# H01R0_Backend.net
KiCad netlist of a schematic drawn in Altium Designer
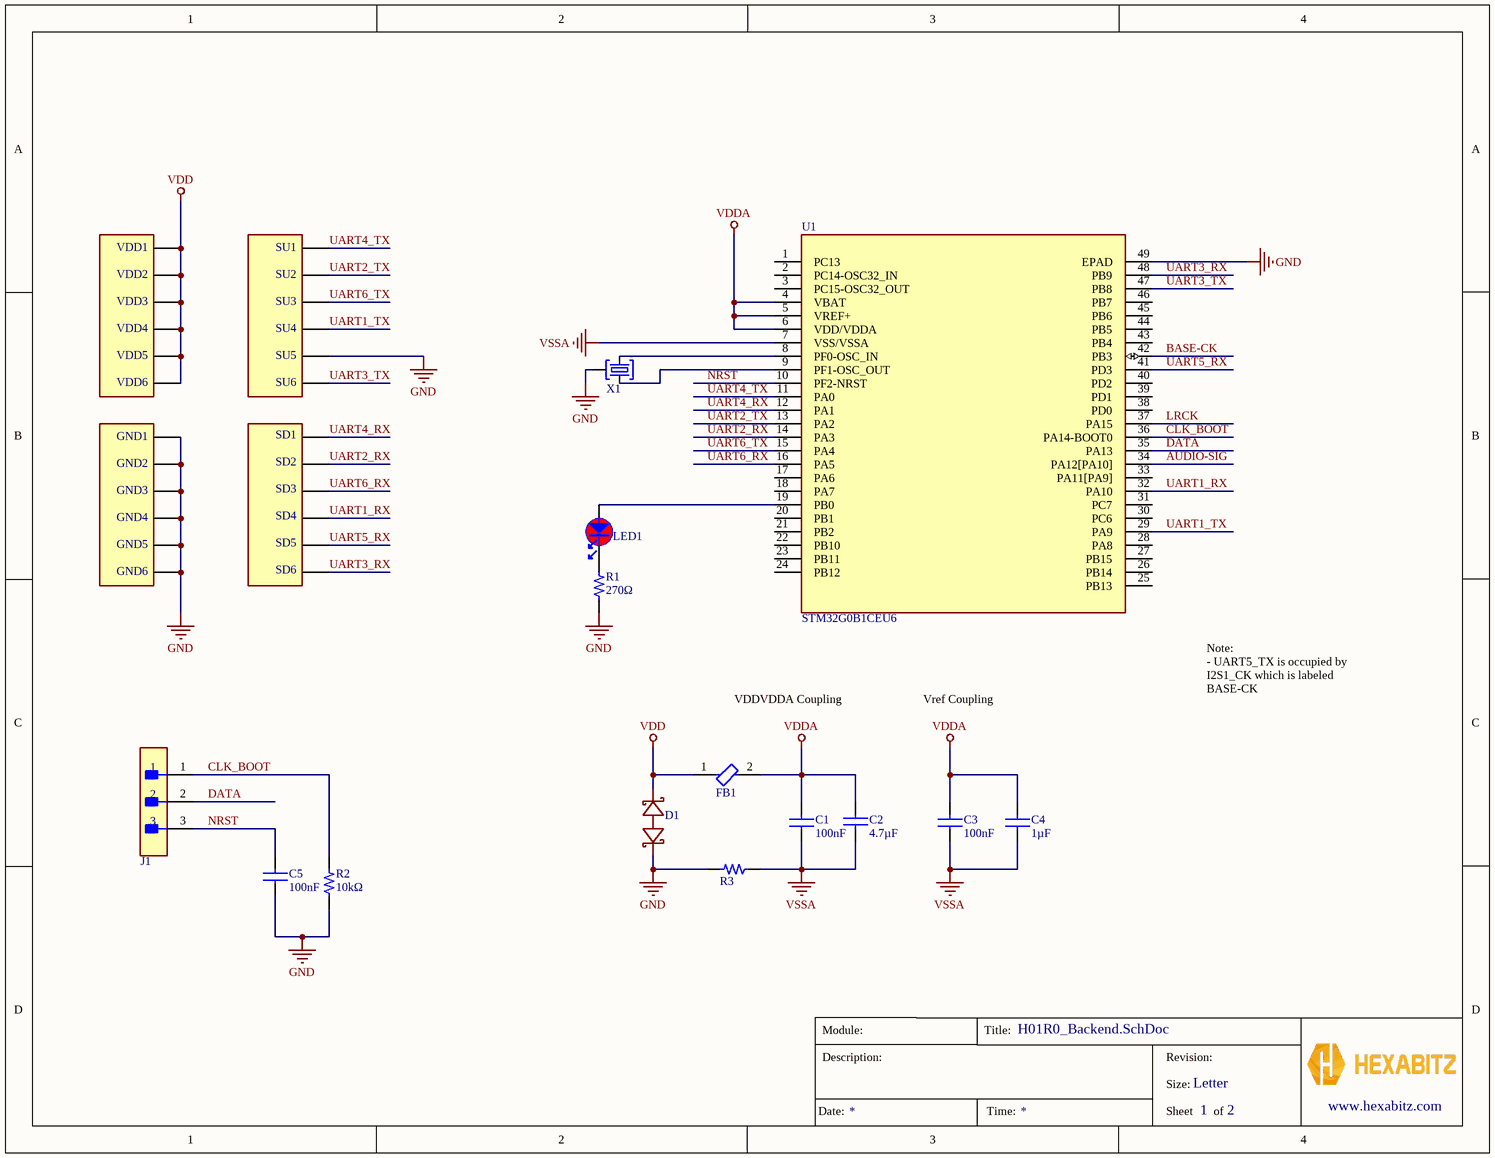
[diagram p0: H01R0_Backend.SchDoc]

(export (version "E")
  (design (tool "Eeschema 10.0.6"))
  (components
    (comp (ref "C1")
      (value "100nF")
      (footprint "C0603")
      (fields
        (field (name "MANUFACTURER") "Samsung Electro-Mechanics")
        (field (name "MANUFACTURER PART NUMBER") "CL10B104KA8NNNC")
        (field (name "TOLERANCE") "10%")
      )
      (libsource (lib "Hexabitz Altium Library") (part "generic Capacitor"))
    )
    (comp (ref "C2")
      (value "4.7µF")
      (footprint "C0805")
      (fields
        (field (name "MANUFACTURER") "Samsung Electro-Mechanics")
        (field (name "MANUFACTURER PART NUMBER") "CL21X475KAQNNNE")
        (field (name "TOLERANCE") "10%")
      )
      (libsource (lib "Hexabitz Altium Library") (part "generic Capacitor"))
    )
    (comp (ref "C3")
      (value "100nF")
      (footprint "C0603")
      (fields
        (field (name "MANUFACTURER") "Samsung Electro-Mechanics")
        (field (name "MANUFACTURER PART NUMBER") "CL10B104KA8NNNC")
        (field (name "TOLERANCE") "10%")
      )
      (libsource (lib "Hexabitz Altium Library") (part "generic Capacitor"))
    )
    (comp (ref "C4")
      (value "1µF")
      (footprint "C0805")
      (description "Ceramic Capacitor, Ceramic, 16V, 10% +Tol, 10% -Tol, X7R, 15% TC, 1uF, Surface Mount, 0805")
      (fields
        (field (name "MANUFACTURER") "Yageo Group")
        (field (name "MANUFACTURER PART NUMBER") "CC0805KKX7R7BB105")
      )
      (libsource (lib "Hexabitz Altium Library") (part "generic Capacitor"))
    )
    (comp (ref "C5")
      (value "100nF")
      (footprint "C0603")
      (fields
        (field (name "MANUFACTURER") "Samsung Electro-Mechanics")
        (field (name "MANUFACTURER PART NUMBER") "CL10B104KA8NNNC")
        (field (name "TOLERANCE") "10%")
      )
      (libsource (lib "Hexabitz Altium Library") (part "generic Capacitor"))
    )
    (comp (ref "D1")
      (value "CDSOD323-T03SC")
      (footprint "SOD2513X114N")
      (description "A 3V, 350W, bi-directional, standard capacitance, SOD323 pkg TVS Diode ¦ Bourns CDSOD323-T03SC")
      (fields (field (name "MANUFACTURER") "Bourns"))
      (libsource (lib "Hexabitz Altium Library") (part "CDSOD323-T03SC"))
    )
    (comp (ref "FB1")
      (value "MMZ1608Y300B")
      (footprint "FP-MMZ1608-0_8-MFG")
      (description "Ferrite Beads 0603 30ohms 1500mA Signal Line AEC-Q200")
      (fields
        (field (name "MANUFACTURER") "TDK")
        (field (name "MANUFACTURER PART NUMBER") "MMZ1608Y300BTD25")
      )
      (libsource (lib "Hexabitz Altium Library") (part "MMZ1608Y300B"))
    )
    (comp (ref "GND1")
      (value "HEXABIT_UART_PORT")
      (footprint "HEXABIT_POWER_PORT_D")
      (libsource (lib "hexabitz_connectors.Library") (part "HEXABIT_POWER_PORT_D"))
    )
    (comp (ref "GND2")
      (value "HEXABIT_UART_PORT")
      (footprint "HEXABIT_POWER_PORT_D")
      (libsource (lib "hexabitz_connectors.Library") (part "HEXABIT_POWER_PORT_D"))
    )
    (comp (ref "GND3")
      (value "HEXABIT_UART_PORT")
      (footprint "HEXABIT_POWER_PORT_D")
      (libsource (lib "hexabitz_connectors.Library") (part "HEXABIT_POWER_PORT_D"))
    )
    (comp (ref "GND4")
      (value "HEXABIT_UART_PORT")
      (footprint "HEXABIT_POWER_PORT_D")
      (libsource (lib "hexabitz_connectors.Library") (part "HEXABIT_POWER_PORT_D"))
    )
    (comp (ref "GND5")
      (value "HEXABIT_UART_PORT")
      (footprint "HEXABIT_POWER_PORT_D")
      (libsource (lib "hexabitz_connectors.Library") (part "HEXABIT_POWER_PORT_D"))
    )
    (comp (ref "GND6")
      (value "HEXABIT_UART_PORT")
      (footprint "HEXABIT_POWER_PORT_D")
      (libsource (lib "hexabitz_connectors.Library") (part "HEXABIT_POWER_PORT_D"))
    )
    (comp (ref "J1")
      (value "TSW-103-14-G-S")
      (footprint "FP-TSW-103-14-G-S-MFG")
      (description "CONN HEADER VERT 3POS 2.54MM")
      (libsource (lib "Altium Content Vault") (part "cd3439d6ef35ae5d9b27ec4fdd3e828"))
    )
    (comp (ref "LED1")
      (value "VLMS1300-GS08")
      (footprint "FP-6_541-5092_01-4-MFG")
      (description "LED Uni-Color Super Red 639nm 2-Pin Chip 0603(1608Metric) T/R")
      (fields (field (name "MANUFACTURER") "Vishay Semiconductors"))
      (libsource (lib "Hexabitz Altium Library") (part "VLMS1300-GS08"))
    )
    (comp (ref "R1")
      (value "270Ω")
      (footprint "R0603")
      (description "Res Thick Film 0603 270 Ohm 5% 0.1W(1/10W) ±200ppm/C Pad SMD Automotive T/R")
      (fields
        (field (name "MANUFACTURER") "Panasonic")
        (field (name "MANUFACTURER PART NUMBER") "ERJ-3GEYJ271V")
      )
      (libsource (lib "Hexabitz Altium Library") (part "generic Resistor"))
    )
    (comp (ref "R2")
      (value "10kΩ")
      (footprint "R0603")
      (description "100mW Thick Film Resistors ±100ppm/℃ ±1% 10kΩ 0603 Chip Resistor - Surface Mount ROHS")
      (fields
        (field (name "MANUFACTURER") "Yageo Group")
        (field (name "MANUFACTURER PART NUMBER") "RC0603FR-0710KL")
      )
      (libsource (lib "") (part "generic Resistor_2"))
    )
    (comp (ref "R3")
      (value "Manufacturer Part Number")
      (footprint "R0603")
      (libsource (lib "") (part "generic Resistor_1"))
    )
    (comp (ref "SD1")
      (value "HEXABIT_UART_PORT")
      (footprint "HEXABIT_UART_PORT_D")
      (libsource (lib "hexabitz_connectors.Library") (part "HEXABIT_UART_PORT_D"))
    )
    (comp (ref "SD2")
      (value "HEXABIT_UART_PORT")
      (footprint "HEXABIT_UART_PORT_D")
      (libsource (lib "hexabitz_connectors.Library") (part "HEXABIT_UART_PORT_D"))
    )
    (comp (ref "SD3")
      (value "HEXABIT_UART_PORT")
      (footprint "HEXABIT_UART_PORT_D")
      (libsource (lib "hexabitz_connectors.Library") (part "HEXABIT_UART_PORT_D"))
    )
    (comp (ref "SD4")
      (value "HEXABIT_UART_PORT")
      (footprint "HEXABIT_UART_PORT_D")
      (libsource (lib "hexabitz_connectors.Library") (part "HEXABIT_UART_PORT_D"))
    )
    (comp (ref "SD5")
      (value "HEXABIT_UART_PORT")
      (footprint "HEXABIT_UART_PORT_D")
      (libsource (lib "hexabitz_connectors.Library") (part "HEXABIT_UART_PORT_D"))
    )
    (comp (ref "SD6")
      (value "HEXABIT_UART_PORT")
      (footprint "HEXABIT_UART_PORT_D")
      (libsource (lib "hexabitz_connectors.Library") (part "HEXABIT_UART_PORT_D"))
    )
    (comp (ref "SU1")
      (value "HEXABIT_UART_PORT")
      (footprint "HEXABIT_UART_PORT_U")
      (libsource (lib "hexabitz_connectors.Library") (part "HEXABIT_UART_PORT_U"))
    )
    (comp (ref "SU2")
      (value "HEXABIT_UART_PORT")
      (footprint "HEXABIT_UART_PORT_U")
      (libsource (lib "hexabitz_connectors.Library") (part "HEXABIT_UART_PORT_U"))
    )
    (comp (ref "SU3")
      (value "HEXABIT_UART_PORT")
      (footprint "HEXABIT_UART_PORT_U")
      (libsource (lib "hexabitz_connectors.Library") (part "HEXABIT_UART_PORT_U"))
    )
    (comp (ref "SU4")
      (value "HEXABIT_UART_PORT")
      (footprint "HEXABIT_UART_PORT_U")
      (libsource (lib "hexabitz_connectors.Library") (part "HEXABIT_UART_PORT_U"))
    )
    (comp (ref "SU5")
      (value "HEXABIT_UART_PORT")
      (footprint "HEXABIT_UART_PORT_U")
      (libsource (lib "hexabitz_connectors.Library") (part "HEXABIT_UART_PORT_U"))
    )
    (comp (ref "SU6")
      (value "HEXABIT_UART_PORT")
      (footprint "HEXABIT_UART_PORT_U")
      (libsource (lib "hexabitz_connectors.Library") (part "HEXABIT_UART_PORT_U"))
    )
    (comp (ref "U1")
      (value "STM32G0B1CEU6")
      (footprint "QFN50P700X700X65-49N-D")
      (description "MCU 32-bit ARM Cortex M0+ RISC 512KB Flash 1.8V/2.5V/3.3V 48-Pin UFQFPN EP Tray")
      (fields
        (field (name "MANUFACTURER") "STMicroelectronics")
        (field (name "MANUFACTURER PART NUMBER") "STM32G0B1CEU6")
      )
      (libsource (lib "Hexabitz Altium Library") (part "STM32G0B1CEU6"))
    )
    (comp (ref "VDD1")
      (value "HEXABIT_UART_PORT")
      (footprint "HEXABIT_POWER_PORT_U")
      (libsource (lib "hexabitz_connectors.Library") (part "HEXABIT_POWER_PORT_U"))
    )
    (comp (ref "VDD2")
      (value "HEXABIT_UART_PORT")
      (footprint "HEXABIT_POWER_PORT_U")
      (libsource (lib "hexabitz_connectors.Library") (part "HEXABIT_POWER_PORT_U"))
    )
    (comp (ref "VDD3")
      (value "HEXABIT_UART_PORT")
      (footprint "HEXABIT_POWER_PORT_U")
      (libsource (lib "hexabitz_connectors.Library") (part "HEXABIT_POWER_PORT_U"))
    )
    (comp (ref "VDD4")
      (value "HEXABIT_UART_PORT")
      (footprint "HEXABIT_POWER_PORT_U")
      (libsource (lib "hexabitz_connectors.Library") (part "HEXABIT_POWER_PORT_U"))
    )
    (comp (ref "VDD5")
      (value "HEXABIT_UART_PORT")
      (footprint "HEXABIT_POWER_PORT_U")
      (libsource (lib "hexabitz_connectors.Library") (part "HEXABIT_POWER_PORT_U"))
    )
    (comp (ref "VDD6")
      (value "HEXABIT_UART_PORT")
      (footprint "HEXABIT_POWER_PORT_U")
      (libsource (lib "hexabitz_connectors.Library") (part "HEXABIT_POWER_PORT_U"))
    )
    (comp (ref "X1")
      (value "CSTCE8M00G52Z-R0")
      (footprint "XTALL_CSTCE8M00G52")
      (description "Ceramic Resonator 8MHz ±0.5% (Tol) ±0.2% (Stability) 10pF 40Ohm 3-Pin CSMD T/R")
      (fields (field (name "MANUFACTURER") "Murata") (field (name "TOLERANCE") "0.5%"))
      (libsource (lib "Hexabitz Altium Library") (part "CSTCE8M00G52Z-R0"))
    )
  )
  (nets
    (net (code "1") (name "/AUDIO-SIG") (class "Default")
      (node (ref "U1") (pin "34") (pinfunction "PA12[PA10]_34") (pintype "passive"))
    )
    (net (code "2") (name "/BASE-CK") (class "Default")
      (node (ref "U1") (pin "42") (pinfunction "PB3_42") (pintype "bidirectional"))
    )
    (net (code "3") (name "/CLK_BOOT") (class "Default")
      (node (ref "J1") (pin "1") (pinfunction "1_1") (pintype "passive"))
      (node (ref "R2") (pin "1") (pinfunction "1_1") (pintype "passive"))
      (node (ref "U1") (pin "36") (pinfunction "PA14-BOOT0_36") (pintype "passive"))
    )
    (net (code "4") (name "/DATA") (class "Default")
      (node (ref "J1") (pin "2") (pinfunction "2_2") (pintype "passive"))
      (node (ref "U1") (pin "35") (pinfunction "PA13_35") (pintype "passive"))
    )
    (net (code "5") (name "/LRCK") (class "Default")
      (node (ref "U1") (pin "37") (pinfunction "PA15_37") (pintype "passive"))
    )
    (net (code "6") (name "/NRST") (class "Default")
      (node (ref "C5") (pin "2") (pinfunction "2_2") (pintype "passive"))
      (node (ref "J1") (pin "3") (pinfunction "3_3") (pintype "passive"))
      (node (ref "U1") (pin "10") (pinfunction "PF2-NRST_10") (pintype "passive"))
    )
    (net (code "7") (name "/UART1_RX") (class "Default")
      (node (ref "SD4") (pin "UART_D") (pinfunction "UART_D_UART_D") (pintype "passive"))
      (node (ref "U1") (pin "32") (pinfunction "PA10_32") (pintype "passive"))
    )
    (net (code "8") (name "/UART1_TX") (class "Default")
      (node (ref "SU4") (pin "UART_U") (pinfunction "UART_U_UART_U") (pintype "passive"))
      (node (ref "U1") (pin "29") (pinfunction "PA9_29") (pintype "passive"))
    )
    (net (code "9") (name "/UART2_RX") (class "Default")
      (node (ref "SD2") (pin "UART_D") (pinfunction "UART_D_UART_D") (pintype "passive"))
      (node (ref "U1") (pin "14") (pinfunction "PA3_14") (pintype "passive"))
    )
    (net (code "10") (name "/UART2_TX") (class "Default")
      (node (ref "SU2") (pin "UART_U") (pinfunction "UART_U_UART_U") (pintype "passive"))
      (node (ref "U1") (pin "13") (pinfunction "PA2_13") (pintype "passive"))
    )
    (net (code "11") (name "/UART3_RX") (class "Default")
      (node (ref "SD6") (pin "UART_D") (pinfunction "UART_D_UART_D") (pintype "passive"))
      (node (ref "U1") (pin "48") (pinfunction "PB9_48") (pintype "passive"))
    )
    (net (code "12") (name "/UART3_TX") (class "Default")
      (node (ref "SU6") (pin "UART_U") (pinfunction "UART_U_UART_U") (pintype "passive"))
      (node (ref "U1") (pin "47") (pinfunction "PB8_47") (pintype "passive"))
    )
    (net (code "13") (name "/UART4_RX") (class "Default")
      (node (ref "SD1") (pin "UART_D") (pinfunction "UART_D_UART_D") (pintype "passive"))
      (node (ref "U1") (pin "12") (pinfunction "PA1_12") (pintype "passive"))
    )
    (net (code "14") (name "/UART4_TX") (class "Default")
      (node (ref "SU1") (pin "UART_U") (pinfunction "UART_U_UART_U") (pintype "passive"))
      (node (ref "U1") (pin "11") (pinfunction "PA0_11") (pintype "passive"))
    )
    (net (code "15") (name "/UART5_RX") (class "Default")
      (node (ref "SD5") (pin "UART_D") (pinfunction "UART_D_UART_D") (pintype "passive"))
      (node (ref "U1") (pin "41") (pinfunction "PD3_41") (pintype "passive"))
    )
    (net (code "16") (name "/UART6_RX") (class "Default")
      (node (ref "SD3") (pin "UART_D") (pinfunction "UART_D_UART_D") (pintype "passive"))
      (node (ref "U1") (pin "16") (pinfunction "PA5_16") (pintype "passive"))
    )
    (net (code "17") (name "/UART6_TX") (class "Default")
      (node (ref "SU3") (pin "UART_U") (pinfunction "UART_U_UART_U") (pintype "passive"))
      (node (ref "U1") (pin "15") (pinfunction "PA4_15") (pintype "passive"))
    )
    (net (code "18") (name "GND") (class "Default")
      (node (ref "C5") (pin "1") (pinfunction "1_1") (pintype "passive"))
      (node (ref "D1") (pin "1") (pinfunction "A_1") (pintype "passive"))
      (node (ref "GND1") (pin "Pwr_D") (pinfunction "Pwr_D_Pwr_D") (pintype "passive"))
      (node (ref "GND2") (pin "Pwr_D") (pinfunction "Pwr_D_Pwr_D") (pintype "passive"))
      (node (ref "GND3") (pin "Pwr_D") (pinfunction "Pwr_D_Pwr_D") (pintype "passive"))
      (node (ref "GND4") (pin "Pwr_D") (pinfunction "Pwr_D_Pwr_D") (pintype "passive"))
      (node (ref "GND5") (pin "Pwr_D") (pinfunction "Pwr_D_Pwr_D") (pintype "passive"))
      (node (ref "GND6") (pin "Pwr_D") (pinfunction "Pwr_D_Pwr_D") (pintype "passive"))
      (node (ref "R1") (pin "1") (pinfunction "1_1") (pintype "passive"))
      (node (ref "R2") (pin "2") (pinfunction "2_2") (pintype "passive"))
      (node (ref "R3") (pin "1") (pinfunction "1_1") (pintype "passive"))
      (node (ref "SU5") (pin "UART_U") (pinfunction "UART_U_UART_U") (pintype "passive"))
      (node (ref "U1") (pin "49") (pinfunction "EPAD_49") (pintype "passive"))
      (node (ref "X1") (pin "P$2") (pinfunction "2_P$2") (pintype "passive"))
    )
    (net (code "19") (name "Net-(LED1-Pad1)") (class "Default")
      (node (ref "LED1") (pin "1") (pintype "passive"))
      (node (ref "R1") (pin "2") (pinfunction "2_2") (pintype "passive"))
    )
    (net (code "20") (name "Net-(U1-PB0)") (class "Default")
      (node (ref "LED1") (pin "2") (pintype "passive"))
      (node (ref "U1") (pin "19") (pinfunction "PB0_19") (pintype "passive"))
    )
    (net (code "21") (name "Net-(U1-PF0-OSC_IN)") (class "Default")
      (node (ref "U1") (pin "8") (pinfunction "PF0-OSC_IN_8") (pintype "passive"))
      (node (ref "X1") (pin "P$3") (pinfunction "3_P$3") (pintype "passive"))
    )
    (net (code "22") (name "Net-(U1-PF1-OSC_OUT)") (class "Default")
      (node (ref "U1") (pin "9") (pinfunction "PF1-OSC_OUT_9") (pintype "passive"))
      (node (ref "X1") (pin "P$1") (pinfunction "1_P$1") (pintype "passive"))
    )
    (net (code "23") (name "VDD") (class "Default")
      (node (ref "D1") (pin "2") (pinfunction "C_2") (pintype "passive"))
      (node (ref "FB1") (pin "1") (pinfunction "1_1") (pintype "passive"))
      (node (ref "VDD1") (pin "Pwr_U") (pinfunction "Pwr_U_Pwr_U") (pintype "passive"))
      (node (ref "VDD2") (pin "Pwr_U") (pinfunction "Pwr_U_Pwr_U") (pintype "passive"))
      (node (ref "VDD3") (pin "Pwr_U") (pinfunction "Pwr_U_Pwr_U") (pintype "passive"))
      (node (ref "VDD4") (pin "Pwr_U") (pinfunction "Pwr_U_Pwr_U") (pintype "passive"))
      (node (ref "VDD5") (pin "Pwr_U") (pinfunction "Pwr_U_Pwr_U") (pintype "passive"))
      (node (ref "VDD6") (pin "Pwr_U") (pinfunction "Pwr_U_Pwr_U") (pintype "passive"))
    )
    (net (code "24") (name "VDDA") (class "Default")
      (node (ref "C1") (pin "2") (pinfunction "2_2") (pintype "passive"))
      (node (ref "C2") (pin "1") (pinfunction "1_1") (pintype "passive"))
      (node (ref "C3") (pin "2") (pinfunction "2_2") (pintype "passive"))
      (node (ref "C4") (pin "2") (pinfunction "2_2") (pintype "passive"))
      (node (ref "FB1") (pin "2") (pinfunction "2_2") (pintype "passive"))
      (node (ref "U1") (pin "4") (pinfunction "VBAT_4") (pintype "passive"))
      (node (ref "U1") (pin "5") (pinfunction "VREF+_5") (pintype "passive"))
      (node (ref "U1") (pin "6") (pinfunction "VDD/VDDA_6") (pintype "passive"))
    )
    (net (code "25") (name "VSSA") (class "Default")
      (node (ref "C1") (pin "1") (pinfunction "1_1") (pintype "passive"))
      (node (ref "C2") (pin "2") (pinfunction "2_2") (pintype "passive"))
      (node (ref "C3") (pin "1") (pinfunction "1_1") (pintype "passive"))
      (node (ref "C4") (pin "1") (pinfunction "1_1") (pintype "passive"))
      (node (ref "R3") (pin "2") (pinfunction "2_2") (pintype "passive"))
      (node (ref "U1") (pin "7") (pinfunction "VSS/VSSA_7") (pintype "passive"))
    )
    (net (code "26") (name "unconnected-(U1-PA6-Pad17)") (class "Default")
      (node (ref "U1") (pin "17") (pinfunction "PA6_17") (pintype "passive"))
    )
    (net (code "27") (name "unconnected-(U1-PA7-Pad18)") (class "Default")
      (node (ref "U1") (pin "18") (pinfunction "PA7_18") (pintype "passive"))
    )
    (net (code "28") (name "unconnected-(U1-PA8-Pad28)") (class "Default")
      (node (ref "U1") (pin "28") (pinfunction "PA8_28") (pintype "passive"))
    )
    (net (code "29") (name "unconnected-(U1-PA11[PA9]-Pad33)") (class "Default")
      (node (ref "U1") (pin "33") (pinfunction "PA11[PA9]_33") (pintype "passive"))
    )
    (net (code "30") (name "unconnected-(U1-PB1-Pad20)") (class "Default")
      (node (ref "U1") (pin "20") (pinfunction "PB1_20") (pintype "passive"))
    )
    (net (code "31") (name "unconnected-(U1-PB2-Pad21)") (class "Default")
      (node (ref "U1") (pin "21") (pinfunction "PB2_21") (pintype "passive"))
    )
    (net (code "32") (name "unconnected-(U1-PB4-Pad43)") (class "Default")
      (node (ref "U1") (pin "43") (pinfunction "PB4_43") (pintype "passive"))
    )
    (net (code "33") (name "unconnected-(U1-PB5-Pad44)") (class "Default")
      (node (ref "U1") (pin "44") (pinfunction "PB5_44") (pintype "passive"))
    )
    (net (code "34") (name "unconnected-(U1-PB6-Pad45)") (class "Default")
      (node (ref "U1") (pin "45") (pinfunction "PB6_45") (pintype "passive"))
    )
    (net (code "35") (name "unconnected-(U1-PB7-Pad46)") (class "Default")
      (node (ref "U1") (pin "46") (pinfunction "PB7_46") (pintype "passive"))
    )
    (net (code "36") (name "unconnected-(U1-PB10-Pad22)") (class "Default")
      (node (ref "U1") (pin "22") (pinfunction "PB10_22") (pintype "passive"))
    )
    (net (code "37") (name "unconnected-(U1-PB11-Pad23)") (class "Default")
      (node (ref "U1") (pin "23") (pinfunction "PB11_23") (pintype "passive"))
    )
    (net (code "38") (name "unconnected-(U1-PB12-Pad24)") (class "Default")
      (node (ref "U1") (pin "24") (pinfunction "PB12_24") (pintype "passive"))
    )
    (net (code "39") (name "unconnected-(U1-PB13-Pad25)") (class "Default")
      (node (ref "U1") (pin "25") (pinfunction "PB13_25") (pintype "passive"))
    )
    (net (code "40") (name "unconnected-(U1-PB14-Pad26)") (class "Default")
      (node (ref "U1") (pin "26") (pinfunction "PB14_26") (pintype "passive"))
    )
    (net (code "41") (name "unconnected-(U1-PB15-Pad27)") (class "Default")
      (node (ref "U1") (pin "27") (pinfunction "PB15_27") (pintype "passive"))
    )
    (net (code "42") (name "unconnected-(U1-PC6-Pad30)") (class "Default")
      (node (ref "U1") (pin "30") (pinfunction "PC6_30") (pintype "passive"))
    )
    (net (code "43") (name "unconnected-(U1-PC7-Pad31)") (class "Default")
      (node (ref "U1") (pin "31") (pinfunction "PC7_31") (pintype "passive"))
    )
    (net (code "44") (name "unconnected-(U1-PC13-Pad1)") (class "Default")
      (node (ref "U1") (pin "1") (pinfunction "PC13_1") (pintype "passive"))
    )
    (net (code "45") (name "unconnected-(U1-PC14-OSC32_IN-Pad2)") (class "Default")
      (node (ref "U1") (pin "2") (pinfunction "PC14-OSC32_IN_2") (pintype "passive"))
    )
    (net (code "46") (name "unconnected-(U1-PC15-OSC32_OUT-Pad3)") (class "Default")
      (node (ref "U1") (pin "3") (pinfunction "PC15-OSC32_OUT_3") (pintype "passive"))
    )
    (net (code "47") (name "unconnected-(U1-PD0-Pad38)") (class "Default")
      (node (ref "U1") (pin "38") (pinfunction "PD0_38") (pintype "passive"))
    )
    (net (code "48") (name "unconnected-(U1-PD1-Pad39)") (class "Default")
      (node (ref "U1") (pin "39") (pinfunction "PD1_39") (pintype "passive"))
    )
    (net (code "49") (name "unconnected-(U1-PD2-Pad40)") (class "Default")
      (node (ref "U1") (pin "40") (pinfunction "PD2_40") (pintype "passive"))
    )
  )
)
